# PCM1792A_MainSche.net
KiCad netlist of a schematic drawn in Altium Designer
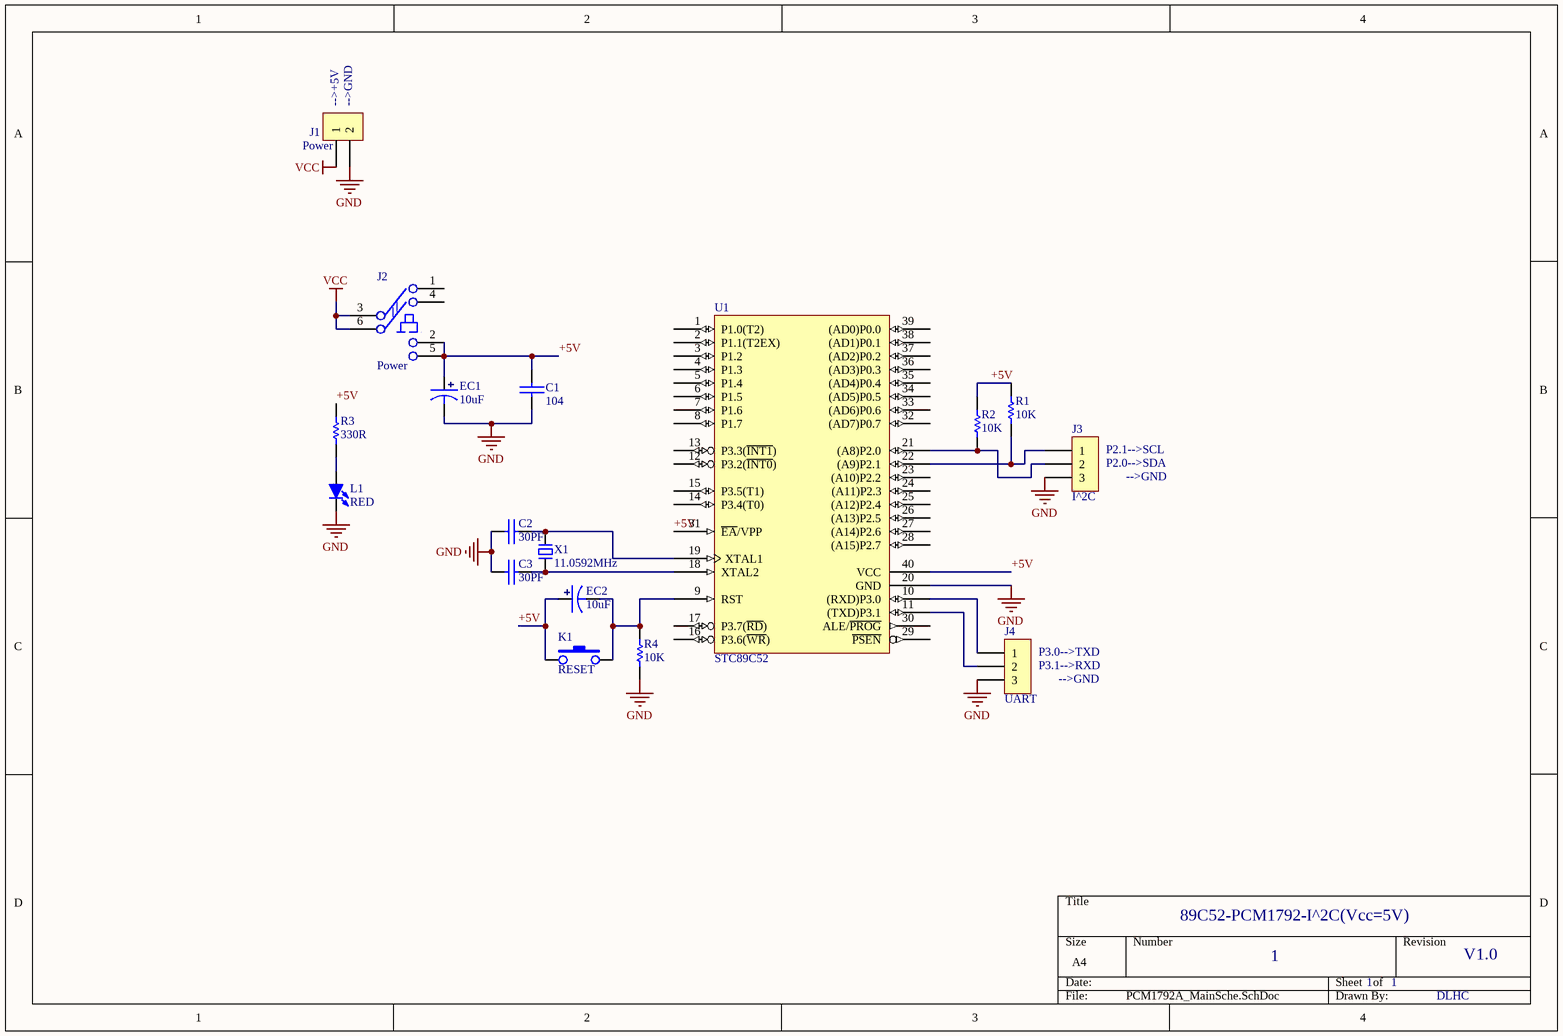
[diagram p0: PCM1792A_MainSche.SchDoc]

(export (version "E")
  (design (tool "Eeschema 10.0.6"))
  (components
    (comp (ref "C1")
      (value "104")
      (footprint "0201C")
      (description "无极性电容")
      (libsource (lib "电容") (part "CAP"))
    )
    (comp (ref "C2")
      (value "30PF")
      (footprint "0201C")
      (description "无极性电容")
      (libsource (lib "电容") (part "CAP"))
    )
    (comp (ref "C3")
      (value "30PF")
      (footprint "0201C")
      (description "无极性电容")
      (libsource (lib "电容") (part "CAP"))
    )
    (comp (ref "EC1")
      (value "10uF")
      (footprint "DIP-EC1.5X4X8")
      (description "直插电解电容")
      (libsource (lib "电容") (part "DIP_ECAP"))
    )
    (comp (ref "EC2")
      (value "10uF")
      (footprint "DIP-EC1.5X4X8")
      (description "直插电解电容")
      (libsource (lib "电容") (part "DIP_ECAP"))
    )
    (comp (ref "J1")
      (value "Power")
      (footprint "Pin HDR1X2/2.54mm-S")
      (libsource (lib "排针") (part "Pin HDR1X2"))
    )
    (comp (ref "J2")
      (value "Power")
      (footprint "KFT DIP-8X8")
      (description "自锁开关")
      (libsource (lib "03 - 按键-开关-晶振-蜂鸣器") (part "KEY-SL"))
    )
    (comp (ref "J3")
      (value "I^2C")
      (footprint "Pin HDR1X3/2.54mm-S")
      (libsource (lib "排针") (part "Pin HDR1X3"))
    )
    (comp (ref "J4")
      (value "UART")
      (footprint "Pin HDR1X3/2.54mm-S")
      (libsource (lib "排针") (part "Pin HDR1X3"))
    )
    (comp (ref "K1") (value "RESET") (footprint "DIP-3X6X4.3") (libsource (lib "轻触开关") (part "KEY")))
    (comp (ref "L1")
      (value "RED")
      (footprint "LED_A1")
      (description "发光二极管")
      (libsource (lib "02 - 二极管(LED)-三极管-整流桥") (part "LED"))
    )
    (comp (ref "R1") (value "10K") (footprint "0201R") (libsource (lib "电阻") (part "RES")))
    (comp (ref "R2") (value "10K") (footprint "0201R") (libsource (lib "电阻") (part "RES")))
    (comp (ref "R3") (value "330R") (footprint "0201R") (libsource (lib "电阻") (part "RES")))
    (comp (ref "R4") (value "10K") (footprint "0201R") (libsource (lib "电阻") (part "RES")))
    (comp (ref "U1") (value "STC89C52") (footprint "DIP40") (libsource (lib "STC系列芯片") (part "STC89C52")))
    (comp (ref "X1")
      (value "11.0592MHz")
      (footprint "OSC HC-49S")
      (description "2脚无源脚晶振")
      (libsource (lib "晶振") (part "XTAL-2P"))
    )
  )
  (nets
    (net (code "1") (name "/+5V") (class "Default")
      (node (ref "C1") (pin "2") (pinfunction "2_2") (pintype "passive"))
      (node (ref "EC1") (pin "1") (pinfunction "1_1") (pintype "passive"))
      (node (ref "EC2") (pin "1") (pinfunction "1_1") (pintype "passive"))
      (node (ref "J2") (pin "2") (pinfunction "2_2") (pintype "passive"))
      (node (ref "J2") (pin "5") (pinfunction "5_5") (pintype "passive"))
      (node (ref "K1") (pin "1") (pinfunction "1_1") (pintype "passive"))
      (node (ref "R1") (pin "2") (pinfunction "2_2") (pintype "passive"))
      (node (ref "R2") (pin "2") (pinfunction "2_2") (pintype "passive"))
      (node (ref "R3") (pin "2") (pinfunction "2_2") (pintype "passive"))
      (node (ref "U1") (pin "31") (pinfunction "~{EA}/VPP_31") (pintype "input"))
      (node (ref "U1") (pin "40") (pinfunction "VCC_40") (pintype "power_in"))
    )
    (net (code "2") (name "GND") (class "Default")
      (node (ref "C1") (pin "1") (pinfunction "1_1") (pintype "passive"))
      (node (ref "C2") (pin "1") (pinfunction "1_1") (pintype "passive"))
      (node (ref "C3") (pin "1") (pinfunction "1_1") (pintype "passive"))
      (node (ref "EC1") (pin "2") (pinfunction "2_2") (pintype "passive"))
      (node (ref "J1") (pin "2") (pinfunction "2_2") (pintype "passive"))
      (node (ref "J3") (pin "3") (pinfunction "3_3") (pintype "passive"))
      (node (ref "J4") (pin "3") (pinfunction "3_3") (pintype "passive"))
      (node (ref "L1") (pin "2") (pinfunction "K_2") (pintype "passive"))
      (node (ref "R4") (pin "1") (pinfunction "1_1") (pintype "passive"))
      (node (ref "U1") (pin "20") (pinfunction "GND_20") (pintype "power_in"))
    )
    (net (code "3") (name "Net-(L1-A)") (class "Default")
      (node (ref "L1") (pin "1") (pinfunction "A_1") (pintype "passive"))
      (node (ref "R3") (pin "1") (pinfunction "1_1") (pintype "passive"))
    )
    (net (code "4") (name "Net-(U1-(A8)P2.0)") (class "Default")
      (node (ref "J3") (pin "2") (pinfunction "2_2") (pintype "passive"))
      (node (ref "R2") (pin "1") (pinfunction "1_1") (pintype "passive"))
      (node (ref "U1") (pin "21") (pinfunction "(A8)P2.0_21") (pintype "bidirectional"))
    )
    (net (code "5") (name "Net-(U1-(A9)P2.1)") (class "Default")
      (node (ref "J3") (pin "1") (pinfunction "1_1") (pintype "passive"))
      (node (ref "R1") (pin "1") (pinfunction "1_1") (pintype "passive"))
      (node (ref "U1") (pin "22") (pinfunction "(A9)P2.1_22") (pintype "bidirectional"))
    )
    (net (code "6") (name "Net-(U1-(RXD)P3.0)") (class "Default")
      (node (ref "J4") (pin "1") (pinfunction "1_1") (pintype "passive"))
      (node (ref "U1") (pin "10") (pinfunction "(RXD)P3.0_10") (pintype "bidirectional"))
    )
    (net (code "7") (name "Net-(U1-(TXD)P3.1)") (class "Default")
      (node (ref "J4") (pin "2") (pinfunction "2_2") (pintype "passive"))
      (node (ref "U1") (pin "11") (pinfunction "(TXD)P3.1_11") (pintype "bidirectional"))
    )
    (net (code "8") (name "Net-(U1-RST)") (class "Default")
      (node (ref "EC2") (pin "2") (pinfunction "2_2") (pintype "passive"))
      (node (ref "K1") (pin "3") (pinfunction "3_3") (pintype "passive"))
      (node (ref "R4") (pin "2") (pinfunction "2_2") (pintype "passive"))
      (node (ref "U1") (pin "9") (pinfunction "RST_9") (pintype "input"))
    )
    (net (code "9") (name "Net-(U1-XTAL1)") (class "Default")
      (node (ref "C2") (pin "2") (pinfunction "2_2") (pintype "passive"))
      (node (ref "U1") (pin "19") (pinfunction "XTAL1_19") (pintype "input"))
      (node (ref "X1") (pin "2") (pinfunction "2_2") (pintype "passive"))
    )
    (net (code "10") (name "Net-(U1-XTAL2)") (class "Default")
      (node (ref "C3") (pin "2") (pinfunction "2_2") (pintype "passive"))
      (node (ref "U1") (pin "18") (pinfunction "XTAL2_18") (pintype "input"))
      (node (ref "X1") (pin "1") (pinfunction "1_1") (pintype "passive"))
    )
    (net (code "11") (name "VCC") (class "Default")
      (node (ref "J1") (pin "1") (pinfunction "1_1") (pintype "passive"))
      (node (ref "J2") (pin "3") (pinfunction "3_3") (pintype "passive"))
      (node (ref "J2") (pin "6") (pinfunction "6_6") (pintype "passive"))
    )
    (net (code "12") (name "unconnected-(J2-Pad1)") (class "Default")
      (node (ref "J2") (pin "1") (pinfunction "1_1") (pintype "passive"))
    )
    (net (code "13") (name "unconnected-(J2-Pad4)") (class "Default")
      (node (ref "J2") (pin "4") (pinfunction "4_4") (pintype "passive"))
    )
    (net (code "14") (name "unconnected-(U1-(A10)P2.2-Pad23)") (class "Default")
      (node (ref "U1") (pin "23") (pinfunction "(A10)P2.2_23") (pintype "bidirectional"))
    )
    (net (code "15") (name "unconnected-(U1-(A11)P2.3-Pad24)") (class "Default")
      (node (ref "U1") (pin "24") (pinfunction "(A11)P2.3_24") (pintype "bidirectional"))
    )
    (net (code "16") (name "unconnected-(U1-(A12)P2.4-Pad25)") (class "Default")
      (node (ref "U1") (pin "25") (pinfunction "(A12)P2.4_25") (pintype "bidirectional"))
    )
    (net (code "17") (name "unconnected-(U1-(A13)P2.5-Pad26)") (class "Default")
      (node (ref "U1") (pin "26") (pinfunction "(A13)P2.5_26") (pintype "bidirectional"))
    )
    (net (code "18") (name "unconnected-(U1-(A14)P2.6-Pad27)") (class "Default")
      (node (ref "U1") (pin "27") (pinfunction "(A14)P2.6_27") (pintype "bidirectional"))
    )
    (net (code "19") (name "unconnected-(U1-(A15)P2.7-Pad28)") (class "Default")
      (node (ref "U1") (pin "28") (pinfunction "(A15)P2.7_28") (pintype "bidirectional"))
    )
    (net (code "20") (name "unconnected-(U1-(AD0)P0.0-Pad39)") (class "Default")
      (node (ref "U1") (pin "39") (pinfunction "(AD0)P0.0_39") (pintype "bidirectional"))
    )
    (net (code "21") (name "unconnected-(U1-(AD1)P0.1-Pad38)") (class "Default")
      (node (ref "U1") (pin "38") (pinfunction "(AD1)P0.1_38") (pintype "bidirectional"))
    )
    (net (code "22") (name "unconnected-(U1-(AD2)P0.2-Pad37)") (class "Default")
      (node (ref "U1") (pin "37") (pinfunction "(AD2)P0.2_37") (pintype "bidirectional"))
    )
    (net (code "23") (name "unconnected-(U1-(AD3)P0.3-Pad36)") (class "Default")
      (node (ref "U1") (pin "36") (pinfunction "(AD3)P0.3_36") (pintype "bidirectional"))
    )
    (net (code "24") (name "unconnected-(U1-(AD4)P0.4-Pad35)") (class "Default")
      (node (ref "U1") (pin "35") (pinfunction "(AD4)P0.4_35") (pintype "bidirectional"))
    )
    (net (code "25") (name "unconnected-(U1-(AD5)P0.5-Pad34)") (class "Default")
      (node (ref "U1") (pin "34") (pinfunction "(AD5)P0.5_34") (pintype "bidirectional"))
    )
    (net (code "26") (name "unconnected-(U1-(AD6)P0.6-Pad33)") (class "Default")
      (node (ref "U1") (pin "33") (pinfunction "(AD6)P0.6_33") (pintype "bidirectional"))
    )
    (net (code "27") (name "unconnected-(U1-(AD7)P0.7-Pad32)") (class "Default")
      (node (ref "U1") (pin "32") (pinfunction "(AD7)P0.7_32") (pintype "bidirectional"))
    )
    (net (code "28") (name "unconnected-(U1-ALE{slash}~{PROG}-Pad30)") (class "Default")
      (node (ref "U1") (pin "30") (pinfunction "ALE/~{PROG}_30") (pintype "output"))
    )
    (net (code "29") (name "unconnected-(U1-P1.0(T2)-Pad1)") (class "Default")
      (node (ref "U1") (pin "1") (pinfunction "P1.0(T2)_1") (pintype "bidirectional"))
    )
    (net (code "30") (name "unconnected-(U1-P1.1(T2EX)-Pad2)") (class "Default")
      (node (ref "U1") (pin "2") (pinfunction "P1.1(T2EX)_2") (pintype "bidirectional"))
    )
    (net (code "31") (name "unconnected-(U1-P1.2-Pad3)") (class "Default")
      (node (ref "U1") (pin "3") (pinfunction "P1.2_3") (pintype "bidirectional"))
    )
    (net (code "32") (name "unconnected-(U1-P1.3-Pad4)") (class "Default")
      (node (ref "U1") (pin "4") (pinfunction "P1.3_4") (pintype "bidirectional"))
    )
    (net (code "33") (name "unconnected-(U1-P1.4-Pad5)") (class "Default")
      (node (ref "U1") (pin "5") (pinfunction "P1.4_5") (pintype "bidirectional"))
    )
    (net (code "34") (name "unconnected-(U1-P1.5-Pad6)") (class "Default")
      (node (ref "U1") (pin "6") (pinfunction "P1.5_6") (pintype "bidirectional"))
    )
    (net (code "35") (name "unconnected-(U1-P1.6-Pad7)") (class "Default")
      (node (ref "U1") (pin "7") (pinfunction "P1.6_7") (pintype "bidirectional"))
    )
    (net (code "36") (name "unconnected-(U1-P1.7-Pad8)") (class "Default")
      (node (ref "U1") (pin "8") (pinfunction "P1.7_8") (pintype "bidirectional"))
    )
    (net (code "37") (name "unconnected-(U1-P3.2(~{INT0})-Pad12)") (class "Default")
      (node (ref "U1") (pin "12") (pinfunction "P3.2(~{INT0})_12") (pintype "bidirectional"))
    )
    (net (code "38") (name "unconnected-(U1-P3.3(~{INT1})-Pad13)") (class "Default")
      (node (ref "U1") (pin "13") (pinfunction "P3.3(~{INT1})_13") (pintype "bidirectional"))
    )
    (net (code "39") (name "unconnected-(U1-P3.4(T0)-Pad14)") (class "Default")
      (node (ref "U1") (pin "14") (pinfunction "P3.4(T0)_14") (pintype "bidirectional"))
    )
    (net (code "40") (name "unconnected-(U1-P3.5(T1)-Pad15)") (class "Default")
      (node (ref "U1") (pin "15") (pinfunction "P3.5(T1)_15") (pintype "bidirectional"))
    )
    (net (code "41") (name "unconnected-(U1-P3.6(~{WR})-Pad16)") (class "Default")
      (node (ref "U1") (pin "16") (pinfunction "P3.6(~{WR})_16") (pintype "bidirectional"))
    )
    (net (code "42") (name "unconnected-(U1-P3.7(~{RD})-Pad17)") (class "Default")
      (node (ref "U1") (pin "17") (pinfunction "P3.7(~{RD})_17") (pintype "bidirectional"))
    )
    (net (code "43") (name "unconnected-(U1-~{PSEN}-Pad29)") (class "Default")
      (node (ref "U1") (pin "29") (pinfunction "~{PSEN}_29") (pintype "output"))
    )
  )
)
